# scheme.net
KiCad netlist of a schematic drawn in EAGLE
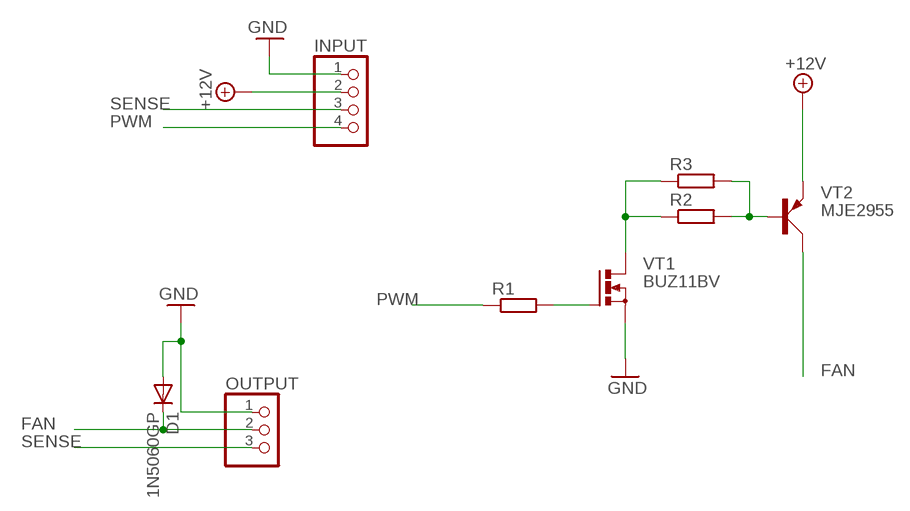
[diagram p0: schematic, sheet 1]

(export (version "E")
  (design (tool "Eeschema 10.0.6"))
  (components
    (comp (ref "D1")
      (value "1N5060GP")
      (footprint "eagle-import:DO15-12")
      (libsource (lib "eagle-import") (part "1N5060GP"))
    )
    (comp (ref "INPUT")
      (value "PINHD-1X4")
      (footprint "eagle-import:1X04")
      (libsource (lib "eagle-import") (part "PINHD-1X4"))
    )
    (comp (ref "OUTPUT")
      (value "PINHD-1X3")
      (footprint "eagle-import:1X03")
      (libsource (lib "eagle-import") (part "PINHD-1X3"))
    )
    (comp (ref "R1")
      (value "R-EU_0204/7")
      (footprint "eagle-import:0204_7")
      (libsource (lib "eagle-import") (part "R-EU_0204/7"))
    )
    (comp (ref "R2")
      (value "R-EU_0411/15")
      (footprint "eagle-import:0411_15")
      (libsource (lib "eagle-import") (part "R-EU_0411/15"))
    )
    (comp (ref "R3")
      (value "R-EU_0411/15")
      (footprint "eagle-import:0411_15")
      (libsource (lib "eagle-import") (part "R-EU_0411/15"))
    )
    (comp (ref "VT1")
      (value "BUZ11BV")
      (footprint "eagle-import:TO220BV")
      (libsource (lib "eagle-import") (part "BUZ11BV"))
    )
    (comp (ref "VT2")
      (value "MJE2955")
      (footprint "eagle-import:TO220AV")
      (libsource (lib "eagle-import") (part "MJE2955"))
    )
  )
  (nets
    (net (code "1") (name "+12V") (class "Default")
      (node (ref "INPUT") (pin "2") (pinfunction "2_2") (pintype "passive"))
      (node (ref "VT2") (pin "E") (pinfunction "E_E") (pintype "passive"))
    )
    (net (code "2") (name "/FAN") (class "Default")
      (node (ref "D1") (pin "C") (pinfunction "C_C") (pintype "passive"))
      (node (ref "OUTPUT") (pin "2") (pinfunction "2_2") (pintype "passive"))
      (node (ref "VT2") (pin "C") (pinfunction "C_C") (pintype "passive"))
    )
    (net (code "3") (name "/PWM") (class "Default")
      (node (ref "INPUT") (pin "4") (pinfunction "4_4") (pintype "passive"))
      (node (ref "R1") (pin "1") (pinfunction "1_1") (pintype "passive"))
    )
    (net (code "4") (name "/SENSE") (class "Default")
      (node (ref "INPUT") (pin "3") (pinfunction "3_3") (pintype "passive"))
      (node (ref "OUTPUT") (pin "3") (pinfunction "3_3") (pintype "passive"))
    )
    (net (code "5") (name "GND") (class "Default")
      (node (ref "D1") (pin "A") (pinfunction "A_A") (pintype "passive"))
      (node (ref "INPUT") (pin "1") (pinfunction "1_1") (pintype "passive"))
      (node (ref "OUTPUT") (pin "1") (pinfunction "1_1") (pintype "passive"))
      (node (ref "VT1") (pin "S") (pinfunction "S_S") (pintype "passive"))
    )
    (net (code "6") (name "Net-(R1-Pad2)") (class "Default")
      (node (ref "R1") (pin "2") (pinfunction "2_2") (pintype "passive"))
      (node (ref "VT1") (pin "G") (pinfunction "G_G") (pintype "passive"))
    )
    (net (code "7") (name "Net-(R2-Pad1)") (class "Default")
      (node (ref "R2") (pin "1") (pinfunction "1_1") (pintype "passive"))
      (node (ref "R3") (pin "1") (pinfunction "1_1") (pintype "passive"))
      (node (ref "VT1") (pin "D") (pinfunction "D_D") (pintype "passive"))
    )
    (net (code "8") (name "Net-(R2-Pad2)") (class "Default")
      (node (ref "R2") (pin "2") (pinfunction "2_2") (pintype "passive"))
      (node (ref "R3") (pin "2") (pinfunction "2_2") (pintype "passive"))
      (node (ref "VT2") (pin "B") (pinfunction "B_B") (pintype "passive"))
    )
  )
)
